# salo.net
KiCad netlist of a schematic drawn in EAGLE
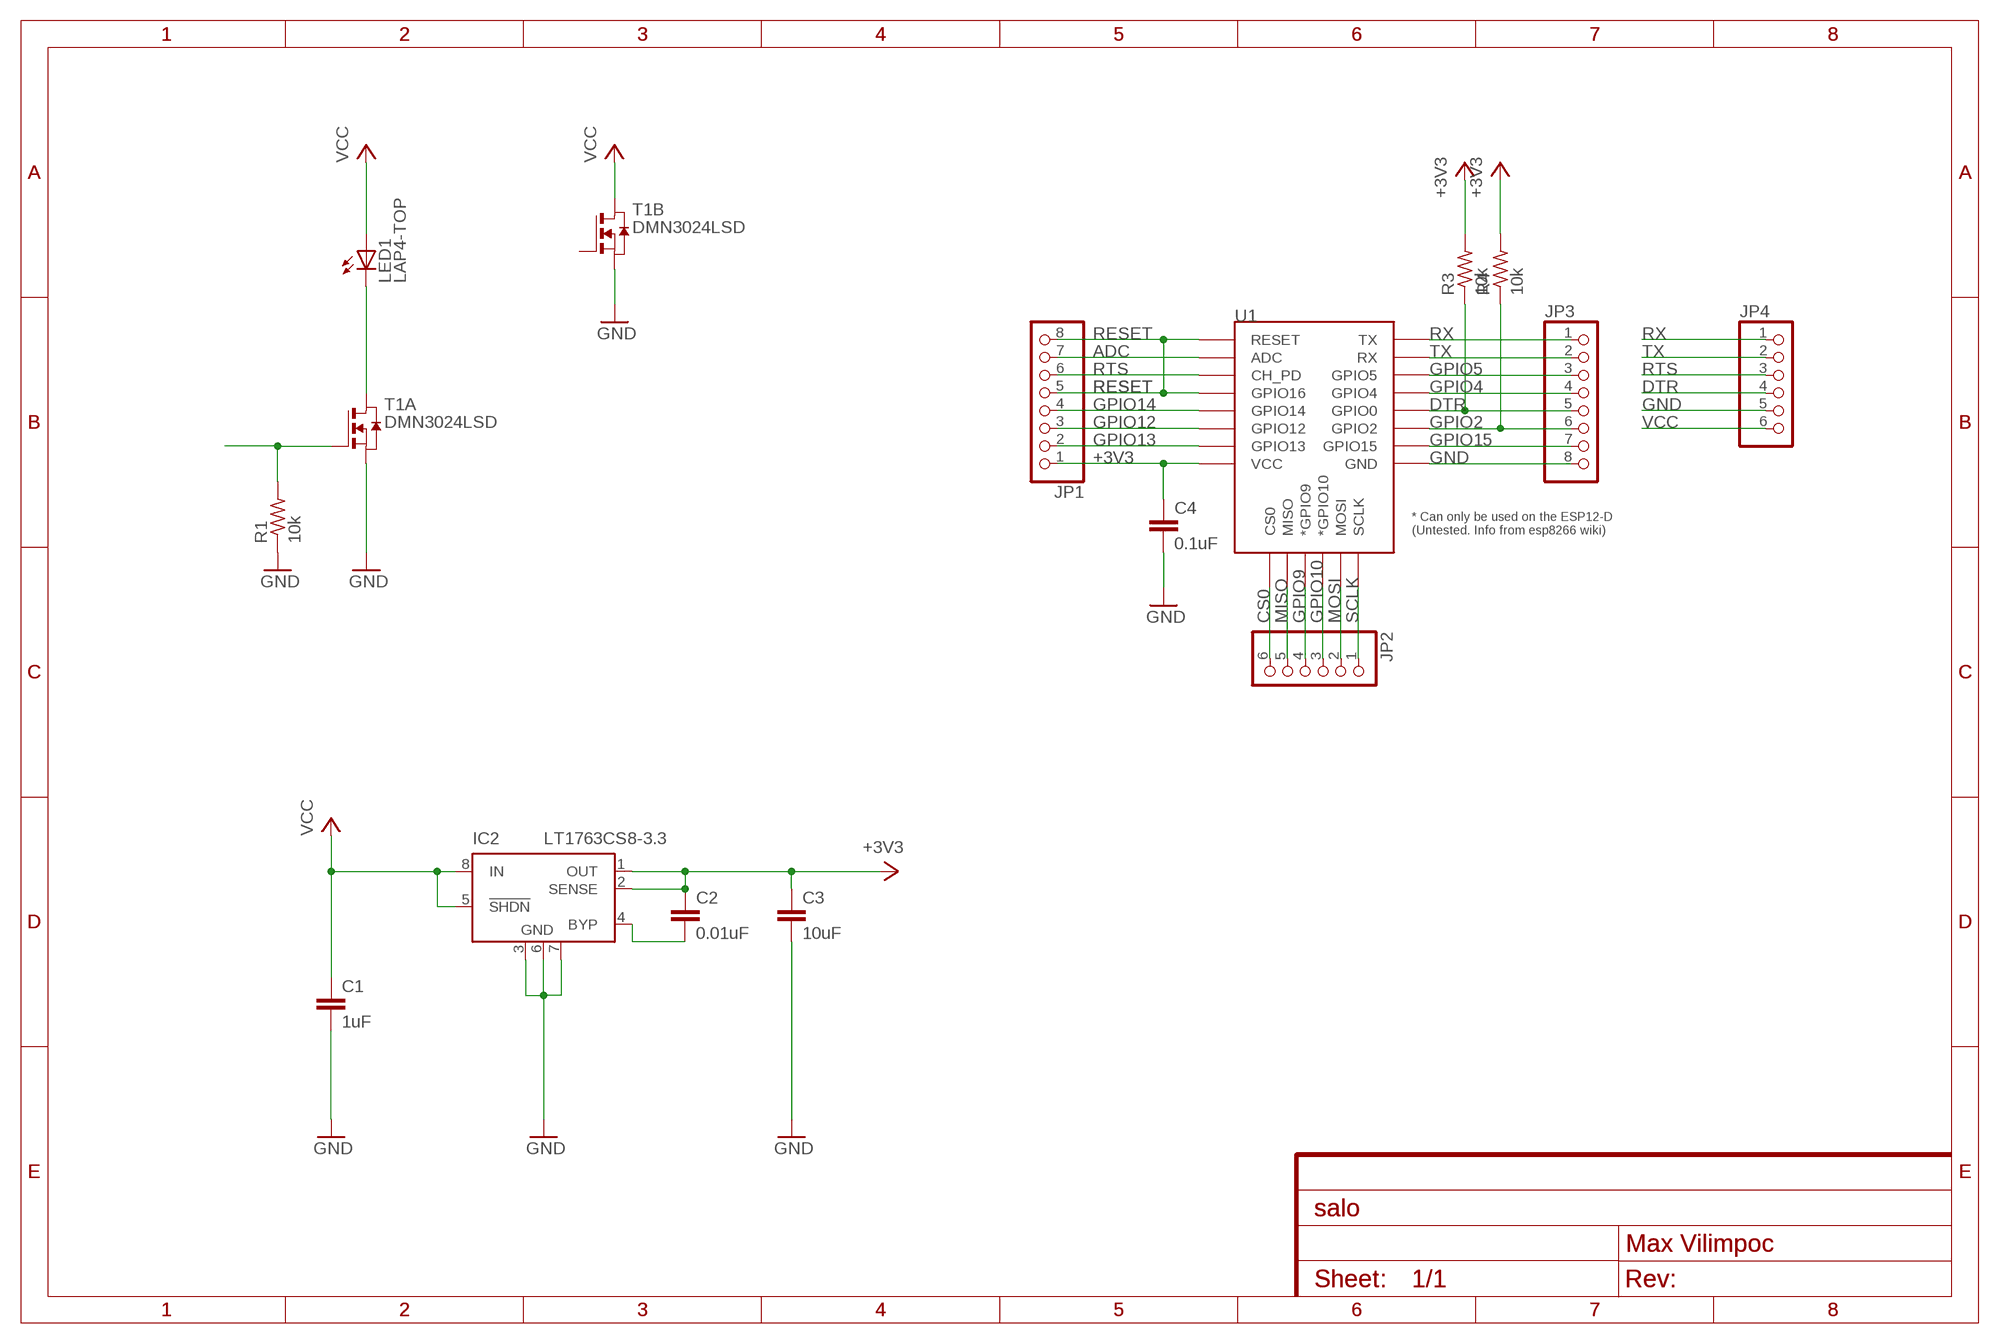
[diagram p0: schematic, sheet 1]

(export (version "E")
  (design (tool "Eeschema 10.0.6"))
  (components
    (comp (ref "C1")
      (value "1uF")
      (footprint "eagle-import:C0805")
      (libsource (lib "eagle-import") (part "C-EUC0805"))
    )
    (comp (ref "C2")
      (value "0.01uF")
      (footprint "eagle-import:C0805")
      (libsource (lib "eagle-import") (part "C-EUC0805"))
    )
    (comp (ref "C3")
      (value "10uF")
      (footprint "eagle-import:C0805")
      (libsource (lib "eagle-import") (part "C-EUC0805"))
    )
    (comp (ref "C4")
      (value "0.1uF")
      (footprint "eagle-import:C0805")
      (libsource (lib "eagle-import") (part "C-EUC0805"))
    )
    (comp (ref "IC2")
      (value "LT1763CS8-3.3")
      (footprint "eagle-import:SOIC8")
      (libsource (lib "eagle-import") (part "LT1763CS8-3.3"))
    )
    (comp (ref "JP1")
      (value "PINHD-1X8")
      (footprint "eagle-import:1X08")
      (libsource (lib "eagle-import") (part "PINHD-1X8"))
    )
    (comp (ref "JP2")
      (value "PINHD-1X6")
      (footprint "eagle-import:1X06")
      (libsource (lib "eagle-import") (part "PINHD-1X6"))
    )
    (comp (ref "JP3")
      (value "PINHD-1X8")
      (footprint "eagle-import:1X08")
      (libsource (lib "eagle-import") (part "PINHD-1X8"))
    )
    (comp (ref "JP4")
      (value "PINHD-1X6")
      (footprint "eagle-import:1X06")
      (libsource (lib "eagle-import") (part "PINHD-1X6"))
    )
    (comp (ref "LED1")
      (value "LAP4-TOP")
      (footprint "eagle-import:P47F-TOP")
      (libsource (lib "eagle-import") (part "P4-TOPLA"))
    )
    (comp (ref "R1")
      (value "10k")
      (footprint "eagle-import:R0805")
      (libsource (lib "eagle-import") (part "R-US_R0805"))
    )
    (comp (ref "R3")
      (value "10k")
      (footprint "eagle-import:R0805")
      (libsource (lib "eagle-import") (part "R-US_R0805"))
    )
    (comp (ref "R4")
      (value "10k")
      (footprint "eagle-import:R0805")
      (libsource (lib "eagle-import") (part "R-US_R0805"))
    )
    (comp (ref "T1")
      (value "DMN3024LSD")
      (footprint "eagle-import:SO8")
      (libsource (lib "eagle-import") (part "DMN3024LSD"))
    )
    (comp (ref "U1")
      (value "ESP12ESMD")
      (footprint "eagle-import:ESP12E-SMD")
      (libsource (lib "eagle-import") (part "ESP12ESMD"))
    )
  )
  (nets
    (net (code "1") (name "+3V3") (class "Default")
      (node (ref "C2") (pin "1") (pinfunction "1_1") (pintype "passive"))
      (node (ref "C3") (pin "1") (pinfunction "1_1") (pintype "passive"))
      (node (ref "C4") (pin "1") (pinfunction "1_1") (pintype "passive"))
      (node (ref "IC2") (pin "1") (pinfunction "OUT_1") (pintype "passive"))
      (node (ref "IC2") (pin "2") (pinfunction "SENSE_2") (pintype "input"))
      (node (ref "JP1") (pin "1") (pinfunction "1_1") (pintype "passive"))
      (node (ref "R3") (pin "2") (pinfunction "2_2") (pintype "passive"))
      (node (ref "R4") (pin "2") (pinfunction "2_2") (pintype "passive"))
      (node (ref "U1") (pin "VCC") (pinfunction "VCC_VCC") (pintype "bidirectional"))
    )
    (net (code "2") (name "/ADC") (class "Default")
      (node (ref "JP1") (pin "7") (pinfunction "7_7") (pintype "passive"))
      (node (ref "U1") (pin "ADC") (pinfunction "ADC_ADC") (pintype "bidirectional"))
    )
    (net (code "3") (name "/CS0") (class "Default")
      (node (ref "JP2") (pin "6") (pinfunction "6_6") (pintype "passive"))
      (node (ref "U1") (pin "CS0") (pinfunction "CS0_CS0") (pintype "bidirectional"))
    )
    (net (code "4") (name "/DTR") (class "Default")
      (node (ref "JP3") (pin "5") (pinfunction "5_5") (pintype "passive"))
      (node (ref "JP4") (pin "4") (pinfunction "4_4") (pintype "passive"))
      (node (ref "R3") (pin "1") (pinfunction "1_1") (pintype "passive"))
      (node (ref "U1") (pin "GPIO0") (pinfunction "GPIO0_GPIO0") (pintype "bidirectional"))
    )
    (net (code "5") (name "/GPIO2") (class "Default")
      (node (ref "JP3") (pin "6") (pinfunction "6_6") (pintype "passive"))
      (node (ref "R4") (pin "1") (pinfunction "1_1") (pintype "passive"))
      (node (ref "U1") (pin "GPIO2") (pinfunction "GPIO2_GPIO2") (pintype "bidirectional"))
    )
    (net (code "6") (name "/GPIO4") (class "Default")
      (node (ref "JP3") (pin "4") (pinfunction "4_4") (pintype "passive"))
      (node (ref "U1") (pin "GPIO4") (pinfunction "GPIO4_GPIO4") (pintype "bidirectional"))
    )
    (net (code "7") (name "/GPIO5") (class "Default")
      (node (ref "JP3") (pin "3") (pinfunction "3_3") (pintype "passive"))
      (node (ref "U1") (pin "GPIO5") (pinfunction "GPIO5_GPIO5") (pintype "bidirectional"))
    )
    (net (code "8") (name "/GPIO9") (class "Default")
      (node (ref "JP2") (pin "4") (pinfunction "4_4") (pintype "passive"))
      (node (ref "U1") (pin "GPIO9") (pinfunction "*GPIO9_GPIO9") (pintype "bidirectional"))
    )
    (net (code "9") (name "/GPIO10") (class "Default")
      (node (ref "JP2") (pin "3") (pinfunction "3_3") (pintype "passive"))
      (node (ref "U1") (pin "GPIO10") (pinfunction "*GPIO10_GPIO10") (pintype "bidirectional"))
    )
    (net (code "10") (name "/GPIO12") (class "Default")
      (node (ref "JP1") (pin "3") (pinfunction "3_3") (pintype "passive"))
      (node (ref "U1") (pin "GPIO12") (pinfunction "GPIO12_GPIO12") (pintype "bidirectional"))
    )
    (net (code "11") (name "/GPIO13") (class "Default")
      (node (ref "JP1") (pin "2") (pinfunction "2_2") (pintype "passive"))
      (node (ref "U1") (pin "GPIO13") (pinfunction "GPIO13_GPIO13") (pintype "bidirectional"))
    )
    (net (code "12") (name "/GPIO14") (class "Default")
      (node (ref "JP1") (pin "4") (pinfunction "4_4") (pintype "passive"))
      (node (ref "U1") (pin "GPIO14") (pinfunction "GPIO14_GPIO14") (pintype "bidirectional"))
    )
    (net (code "13") (name "/GPIO15") (class "Default")
      (node (ref "JP3") (pin "7") (pinfunction "7_7") (pintype "passive"))
      (node (ref "U1") (pin "GPIO15") (pinfunction "GPIO15_GPIO15") (pintype "bidirectional"))
    )
    (net (code "14") (name "/MISO") (class "Default")
      (node (ref "JP2") (pin "5") (pinfunction "5_5") (pintype "passive"))
      (node (ref "U1") (pin "MISO") (pinfunction "MISO_MISO") (pintype "bidirectional"))
    )
    (net (code "15") (name "/MOSI") (class "Default")
      (node (ref "JP2") (pin "2") (pinfunction "2_2") (pintype "passive"))
      (node (ref "U1") (pin "MOSI") (pinfunction "MOSI_MOSI") (pintype "bidirectional"))
    )
    (net (code "16") (name "/RESET") (class "Default")
      (node (ref "JP1") (pin "5") (pinfunction "5_5") (pintype "passive"))
      (node (ref "JP1") (pin "8") (pinfunction "8_8") (pintype "passive"))
      (node (ref "U1") (pin "GPIO16") (pinfunction "GPIO16_GPIO16") (pintype "bidirectional"))
      (node (ref "U1") (pin "RESET") (pinfunction "RESET_RESET") (pintype "bidirectional"))
    )
    (net (code "17") (name "/RTS") (class "Default")
      (node (ref "JP1") (pin "6") (pinfunction "6_6") (pintype "passive"))
      (node (ref "JP4") (pin "3") (pinfunction "3_3") (pintype "passive"))
      (node (ref "U1") (pin "CH_PD") (pinfunction "CH_PD_CH_PD") (pintype "bidirectional"))
    )
    (net (code "18") (name "/RX") (class "Default")
      (node (ref "JP3") (pin "1") (pinfunction "1_1") (pintype "passive"))
      (node (ref "JP4") (pin "1") (pinfunction "1_1") (pintype "passive"))
      (node (ref "U1") (pin "TXD0") (pinfunction "TX_TXD0") (pintype "bidirectional"))
    )
    (net (code "19") (name "/SCLK") (class "Default")
      (node (ref "JP2") (pin "1") (pinfunction "1_1") (pintype "passive"))
      (node (ref "U1") (pin "SCLK") (pinfunction "SCLK_SCLK") (pintype "bidirectional"))
    )
    (net (code "20") (name "/TX") (class "Default")
      (node (ref "JP3") (pin "2") (pinfunction "2_2") (pintype "passive"))
      (node (ref "JP4") (pin "2") (pinfunction "2_2") (pintype "passive"))
      (node (ref "U1") (pin "RXD0") (pinfunction "RX_RXD0") (pintype "bidirectional"))
    )
    (net (code "21") (name "GND") (class "Default")
      (node (ref "C1") (pin "2") (pinfunction "2_2") (pintype "passive"))
      (node (ref "C3") (pin "2") (pinfunction "2_2") (pintype "passive"))
      (node (ref "C4") (pin "2") (pinfunction "2_2") (pintype "passive"))
      (node (ref "IC2") (pin "3") (pinfunction "GND_3") (pintype "power_in"))
      (node (ref "IC2") (pin "6") (pinfunction "GND_6") (pintype "power_in"))
      (node (ref "IC2") (pin "7") (pinfunction "GND_7") (pintype "power_in"))
      (node (ref "JP3") (pin "8") (pinfunction "8_8") (pintype "passive"))
      (node (ref "JP4") (pin "5") (pinfunction "5_5") (pintype "passive"))
      (node (ref "R1") (pin "1") (pinfunction "1_1") (pintype "passive"))
      (node (ref "T1") (pin "1") (pinfunction "S_1") (pintype "passive"))
      (node (ref "T1") (pin "3") (pinfunction "S_3") (pintype "passive"))
      (node (ref "U1") (pin "GND") (pinfunction "GND_GND") (pintype "bidirectional"))
    )
    (net (code "22") (name "Net-(IC2-BYP)") (class "Default")
      (node (ref "C2") (pin "2") (pinfunction "2_2") (pintype "passive"))
      (node (ref "IC2") (pin "4") (pinfunction "BYP_4") (pintype "input"))
    )
    (net (code "23") (name "Net-(LED1-PadC)") (class "Default")
      (node (ref "LED1") (pin "C") (pinfunction "C_C") (pintype "passive"))
      (node (ref "T1") (pin "7") (pinfunction "D_7") (pintype "passive"))
      (node (ref "T1") (pin "8") (pinfunction "D_8") (pintype "passive"))
    )
    (net (code "24") (name "Net-(T1A-G)") (class "Default")
      (node (ref "R1") (pin "2") (pinfunction "2_2") (pintype "passive"))
      (node (ref "T1") (pin "2") (pinfunction "G_2") (pintype "passive"))
    )
    (net (code "25") (name "VCC") (class "Default")
      (node (ref "C1") (pin "1") (pinfunction "1_1") (pintype "passive"))
      (node (ref "IC2") (pin "5") (pinfunction "~{SHDN}_5") (pintype "input"))
      (node (ref "IC2") (pin "8") (pinfunction "IN_8") (pintype "input"))
      (node (ref "JP4") (pin "6") (pinfunction "6_6") (pintype "passive"))
      (node (ref "LED1") (pin "A") (pinfunction "A_A") (pintype "passive"))
      (node (ref "T1") (pin "5") (pinfunction "D_5") (pintype "passive"))
      (node (ref "T1") (pin "6") (pinfunction "D_6") (pintype "passive"))
    )
    (net (code "26") (name "unconnected-(T1B-G-Pad4)") (class "Default")
      (node (ref "T1") (pin "4") (pinfunction "G_4") (pintype "passive"))
    )
  )
)
